# MCU_144_POWER.net
KiCad netlist of a schematic drawn in Altium Designer
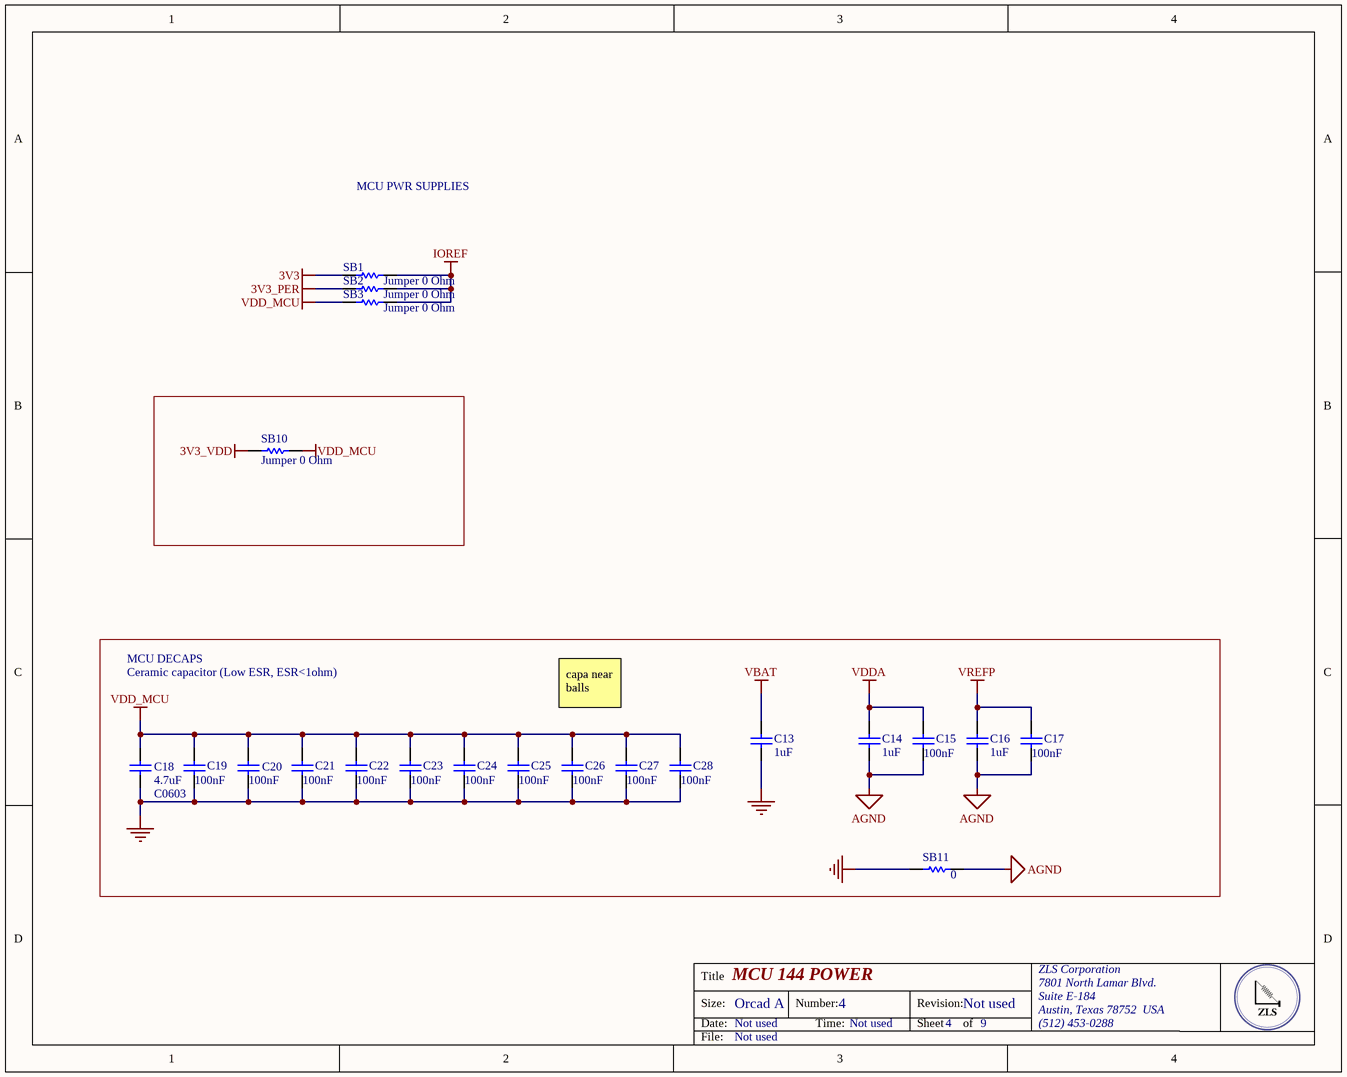
[diagram p0: MCU_144_POWER.SchDoc]

(export (version "E")
  (design (tool "Eeschema 10.0.6"))
  (components
    (comp (ref "C13")
      (value "1uF")
      (footprint "C0603")
      (description "Capacitor, MLCC, 1uF, 6V3, X5R, 10%, 0603, T=0,8mm")
      (fields
        (field (name "INTERNAL_PART_NUMBER") "MCD-00238")
        (field (name "MANUFACTURER_PART_NUMBER") "CC0603KRX5R5BB105")
        (field (name "PROVIDED_BY") "SUBCO")
      )
      (libsource (lib "MCD_PARTS_database") (part "Capacitor"))
    )
    (comp (ref "C14")
      (value "1uF")
      (footprint "C0603")
      (description "Capacitor, MLCC, 1uF, 6V3, X5R, 10%, 0603, T=0,8mm")
      (fields
        (field (name "INTERNAL_PART_NUMBER") "MCD-00238")
        (field (name "MANUFACTURER_PART_NUMBER") "CC0603KRX5R5BB105")
        (field (name "PROVIDED_BY") "SUBCO")
      )
      (libsource (lib "MCD_PARTS_database") (part "Capacitor"))
    )
    (comp (ref "C15")
      (value "Capacitor")
      (footprint "C0402")
      (description "CAP CER 0.1UF 16V X7R 0402")
      (fields
        (field (name "MANUFACTURER") "Yageo")
        (field (name "MANUFACTURER PART NUMBER") "CC0402KRX7R7BB104")
        (field (name "CAPACITANCE") "100nF")
      )
      (libsource (lib "MCD_PARTS_database") (part "Capacitor"))
    )
    (comp (ref "C16")
      (value "1uF")
      (footprint "C0603")
      (description "Capacitor, MLCC, 1uF, 6V3, X5R, 10%, 0603, T=0,8mm")
      (fields
        (field (name "INTERNAL_PART_NUMBER") "MCD-00238")
        (field (name "MANUFACTURER_PART_NUMBER") "CC0603KRX5R5BB105")
        (field (name "PROVIDED_BY") "SUBCO")
      )
      (libsource (lib "MCD_PARTS_database") (part "Capacitor"))
    )
    (comp (ref "C17")
      (value "Capacitor")
      (footprint "C0402")
      (description "CAP CER 0.1UF 16V X7R 0402")
      (fields
        (field (name "MANUFACTURER") "Yageo")
        (field (name "MANUFACTURER PART NUMBER") "CC0402KRX7R7BB104")
        (field (name "CAPACITANCE") "100nF")
      )
      (libsource (lib "MCD_PARTS_database") (part "Capacitor"))
    )
    (comp (ref "C18")
      (value "4.7uF")
      (footprint "C0603")
      (description "Capacitor, MLCC, 4.7µF, 10V, X5R, 20%, 0603, T=0,8mm")
      (fields
        (field (name "INTERNAL_PART_NUMBER") "MCD-01121")
        (field (name "MANUFACTURER_PART_NUMBER") "GRM188R61A475ME15")
        (field (name "PACKAGE") "C0603")
        (field (name "PROVIDED_BY") "SUBCO")
      )
      (libsource (lib "MCD_PARTS_database") (part "Capacitor"))
    )
    (comp (ref "C19")
      (value "Capacitor")
      (footprint "C0402")
      (description "CAP CER 0.1UF 16V X7R 0402")
      (fields
        (field (name "MANUFACTURER") "Yageo")
        (field (name "MANUFACTURER PART NUMBER") "CC0402KRX7R7BB104")
        (field (name "CAPACITANCE") "100nF")
      )
      (libsource (lib "MCD_PARTS_database") (part "Capacitor"))
    )
    (comp (ref "C20")
      (value "Capacitor")
      (footprint "C0402")
      (description "CAP CER 0.1UF 16V X7R 0402")
      (fields
        (field (name "MANUFACTURER") "Yageo")
        (field (name "MANUFACTURER PART NUMBER") "CC0402KRX7R7BB104")
        (field (name "CAPACITANCE") "100nF")
      )
      (libsource (lib "MCD_PARTS_database") (part "Capacitor"))
    )
    (comp (ref "C21")
      (value "Capacitor")
      (footprint "C0402")
      (description "CAP CER 0.1UF 16V X7R 0402")
      (fields
        (field (name "MANUFACTURER") "Yageo")
        (field (name "MANUFACTURER PART NUMBER") "CC0402KRX7R7BB104")
        (field (name "CAPACITANCE") "100nF")
      )
      (libsource (lib "MCD_PARTS_database") (part "Capacitor"))
    )
    (comp (ref "C22")
      (value "Capacitor")
      (footprint "C0402")
      (description "CAP CER 0.1UF 16V X7R 0402")
      (fields
        (field (name "MANUFACTURER") "Yageo")
        (field (name "MANUFACTURER PART NUMBER") "CC0402KRX7R7BB104")
        (field (name "CAPACITANCE") "100nF")
      )
      (libsource (lib "MCD_PARTS_database") (part "Capacitor"))
    )
    (comp (ref "C23")
      (value "Capacitor")
      (footprint "C0402")
      (description "CAP CER 0.1UF 16V X7R 0402")
      (fields
        (field (name "MANUFACTURER") "Yageo")
        (field (name "MANUFACTURER PART NUMBER") "CC0402KRX7R7BB104")
        (field (name "CAPACITANCE") "100nF")
      )
      (libsource (lib "MCD_PARTS_database") (part "Capacitor"))
    )
    (comp (ref "C24")
      (value "Capacitor")
      (footprint "C0402")
      (description "CAP CER 0.1UF 16V X7R 0402")
      (fields
        (field (name "MANUFACTURER") "Yageo")
        (field (name "MANUFACTURER PART NUMBER") "CC0402KRX7R7BB104")
        (field (name "CAPACITANCE") "100nF")
      )
      (libsource (lib "MCD_PARTS_database") (part "Capacitor"))
    )
    (comp (ref "C25")
      (value "Capacitor")
      (footprint "C0402")
      (description "CAP CER 0.1UF 16V X7R 0402")
      (fields
        (field (name "MANUFACTURER") "Yageo")
        (field (name "MANUFACTURER PART NUMBER") "CC0402KRX7R7BB104")
        (field (name "CAPACITANCE") "100nF")
      )
      (libsource (lib "MCD_PARTS_database") (part "Capacitor"))
    )
    (comp (ref "C26")
      (value "Capacitor")
      (footprint "C0402")
      (description "CAP CER 0.1UF 16V X7R 0402")
      (fields
        (field (name "MANUFACTURER") "Yageo")
        (field (name "MANUFACTURER PART NUMBER") "CC0402KRX7R7BB104")
        (field (name "CAPACITANCE") "100nF")
      )
      (libsource (lib "MCD_PARTS_database") (part "Capacitor"))
    )
    (comp (ref "C27")
      (value "Capacitor")
      (footprint "C0402")
      (description "CAP CER 0.1UF 16V X7R 0402")
      (fields
        (field (name "MANUFACTURER") "Yageo")
        (field (name "MANUFACTURER PART NUMBER") "CC0402KRX7R7BB104")
        (field (name "CAPACITANCE") "100nF")
      )
      (libsource (lib "MCD_PARTS_database") (part "Capacitor"))
    )
    (comp (ref "C28")
      (value "Capacitor")
      (footprint "C0402")
      (description "CAP CER 0.1UF 16V X7R 0402")
      (fields
        (field (name "MANUFACTURER") "Yageo")
        (field (name "MANUFACTURER PART NUMBER") "CC0402KRX7R7BB104")
        (field (name "CAPACITANCE") "100nF")
      )
      (libsource (lib "MCD_PARTS_database") (part "Capacitor"))
    )
    (comp (ref "SB1")
      (value "Jumper 0 Ohm")
      (footprint "RESC1608X55X25ML10T15")
      (description "Chip Resistor, 0 Ohm, +/- 5%, 0.1 W, -55 to 155 degC, 0603 (1608 Metric), RoHS, Tape and Reel")
      (fields (field (name "TOLERANCE") "5%") (field (name "MANUFACTURER") "Yageo"))
      (libsource (lib "Altium Content Vault") (part "RES-2"))
    )
    (comp (ref "SB2")
      (value "Jumper 0 Ohm")
      (footprint "RESC1608X55X25ML10T15")
      (description "Chip Resistor, 0 Ohm, +/- 5%, 0.1 W, -55 to 155 degC, 0603 (1608 Metric), RoHS, Tape and Reel")
      (fields (field (name "TOLERANCE") "5%") (field (name "MANUFACTURER") "Yageo"))
      (libsource (lib "Altium Content Vault") (part "RES-2"))
    )
    (comp (ref "SB3")
      (value "Jumper 0 Ohm")
      (footprint "RESC1608X55X25ML10T15")
      (description "Chip Resistor, 0 Ohm, +/- 5%, 0.1 W, -55 to 155 degC, 0603 (1608 Metric), RoHS, Tape and Reel")
      (fields (field (name "TOLERANCE") "5%") (field (name "MANUFACTURER") "Yageo"))
      (libsource (lib "Altium Content Vault") (part "RES-2"))
    )
    (comp (ref "SB10")
      (value "Jumper 0 Ohm")
      (footprint "RESC1608X55X25ML10T15")
      (description "Chip Resistor, 0 Ohm, +/- 5%, 0.1 W, -55 to 155 degC, 0603 (1608 Metric), RoHS, Tape and Reel")
      (fields (field (name "TOLERANCE") "5%") (field (name "MANUFACTURER") "Yageo"))
      (libsource (lib "Altium Content Vault") (part "RES-2"))
    )
    (comp (ref "SB11")
      (value "0")
      (footprint "RESC1608X55X25ML10T15")
      (description "Chip Resistor, 0 Ohm, +/- 5%, 0.1 W, -55 to 155 degC, 0603 (1608 Metric), RoHS, Tape and Reel")
      (fields (field (name "TOLERANCE") "5%") (field (name "MANUFACTURER") "Yageo"))
      (libsource (lib "Altium Content Vault") (part "RES-2"))
    )
  )
  (nets
    (net (code "1") (name "3V3") (class "Default")
      (node (ref "SB1") (pin "1") (pinfunction "1_1") (pintype "passive"))
    )
    (net (code "2") (name "3V3_PER") (class "Default")
      (node (ref "SB2") (pin "1") (pinfunction "1_1") (pintype "passive"))
    )
    (net (code "3") (name "3V3_VDD") (class "Default")
      (node (ref "SB10") (pin "1") (pinfunction "1_1") (pintype "passive"))
    )
    (net (code "4") (name "AGND") (class "Default")
      (node (ref "C14") (pin "2") (pinfunction "2_2") (pintype "passive"))
      (node (ref "C15") (pin "1") (pinfunction "1_1") (pintype "passive"))
      (node (ref "C16") (pin "2") (pinfunction "2_2") (pintype "passive"))
      (node (ref "C17") (pin "1") (pinfunction "1_1") (pintype "passive"))
      (node (ref "SB11") (pin "2") (pinfunction "2_2") (pintype "passive"))
    )
    (net (code "5") (name "GND") (class "Default")
      (node (ref "C13") (pin "1") (pinfunction "1_1") (pintype "passive"))
      (node (ref "C18") (pin "1") (pinfunction "1_1") (pintype "passive"))
      (node (ref "C19") (pin "1") (pinfunction "1_1") (pintype "passive"))
      (node (ref "C20") (pin "1") (pinfunction "1_1") (pintype "passive"))
      (node (ref "C21") (pin "1") (pinfunction "1_1") (pintype "passive"))
      (node (ref "C22") (pin "1") (pinfunction "1_1") (pintype "passive"))
      (node (ref "C23") (pin "1") (pinfunction "1_1") (pintype "passive"))
      (node (ref "C24") (pin "1") (pinfunction "1_1") (pintype "passive"))
      (node (ref "C25") (pin "1") (pinfunction "1_1") (pintype "passive"))
      (node (ref "C26") (pin "1") (pinfunction "1_1") (pintype "passive"))
      (node (ref "C27") (pin "1") (pinfunction "1_1") (pintype "passive"))
      (node (ref "C28") (pin "1") (pinfunction "1_1") (pintype "passive"))
      (node (ref "SB11") (pin "1") (pinfunction "1_1") (pintype "passive"))
    )
    (net (code "6") (name "IOREF") (class "Default")
      (node (ref "SB1") (pin "2") (pinfunction "2_2") (pintype "passive"))
      (node (ref "SB2") (pin "2") (pinfunction "2_2") (pintype "passive"))
      (node (ref "SB3") (pin "2") (pinfunction "2_2") (pintype "passive"))
    )
    (net (code "7") (name "VBAT") (class "Default")
      (node (ref "C13") (pin "2") (pinfunction "2_2") (pintype "passive"))
    )
    (net (code "8") (name "VDDA") (class "Default")
      (node (ref "C14") (pin "1") (pinfunction "1_1") (pintype "passive"))
      (node (ref "C15") (pin "2") (pinfunction "2_2") (pintype "passive"))
    )
    (net (code "9") (name "VDD_MCU") (class "Default")
      (node (ref "C18") (pin "2") (pinfunction "2_2") (pintype "passive"))
      (node (ref "C19") (pin "2") (pinfunction "2_2") (pintype "passive"))
      (node (ref "C20") (pin "2") (pinfunction "2_2") (pintype "passive"))
      (node (ref "C21") (pin "2") (pinfunction "2_2") (pintype "passive"))
      (node (ref "C22") (pin "2") (pinfunction "2_2") (pintype "passive"))
      (node (ref "C23") (pin "2") (pinfunction "2_2") (pintype "passive"))
      (node (ref "C24") (pin "2") (pinfunction "2_2") (pintype "passive"))
      (node (ref "C25") (pin "2") (pinfunction "2_2") (pintype "passive"))
      (node (ref "C26") (pin "2") (pinfunction "2_2") (pintype "passive"))
      (node (ref "C27") (pin "2") (pinfunction "2_2") (pintype "passive"))
      (node (ref "C28") (pin "2") (pinfunction "2_2") (pintype "passive"))
      (node (ref "SB10") (pin "2") (pinfunction "2_2") (pintype "passive"))
      (node (ref "SB3") (pin "1") (pinfunction "1_1") (pintype "passive"))
    )
    (net (code "10") (name "VREFP") (class "Default")
      (node (ref "C16") (pin "1") (pinfunction "1_1") (pintype "passive"))
      (node (ref "C17") (pin "2") (pinfunction "2_2") (pintype "passive"))
    )
  )
)
